# design.net
KiCad netlist of a schematic drawn in Altium Designer
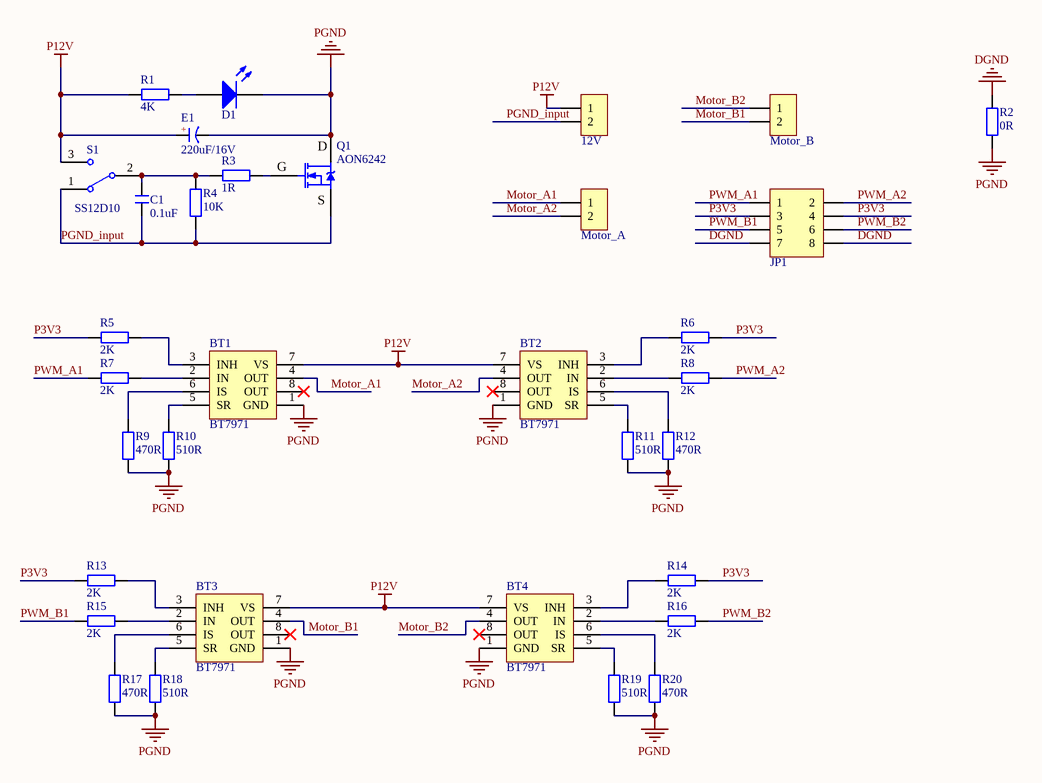
[diagram p0: 驱动开关.SchDoc]

(export (version "E")
  (design (tool "Eeschema 10.0.6"))
  (components
    (comp (ref "12V")
      (value "HDR-1X2")
      (footprint "KF301-5.0-2P")
      (description "2P接插件")
      (fields (field (name "版权归属") "封装库来自淘宝 ID：黄晶宝石"))
      (libsource (lib "6.0 - 接插件-脚距5.0") (part "Header 2"))
    )
    (comp (ref "BT1")
      (value "BT7971")
      (footprint "TO263-7A")
      (libsource (lib "altium-import") (part "root_0_BTN7971_"))
    )
    (comp (ref "BT2")
      (value "BT7971")
      (footprint "TO263-7A")
      (libsource (lib "altium-import") (part "root_0_mirrored_BTN7971_"))
    )
    (comp (ref "BT3")
      (value "BT7971")
      (footprint "TO263-7A")
      (libsource (lib "altium-import") (part "root_0_BTN7971_"))
    )
    (comp (ref "BT4")
      (value "BT7971")
      (footprint "TO263-7A")
      (libsource (lib "altium-import") (part "root_0_mirrored_BTN7971_"))
    )
    (comp (ref "C1")
      (value "0.1uF")
      (footprint "C 0603_L")
      (description "贴片电容")
      (libsource (lib "0.1 - 电阻-电容-电感") (part "C"))
    )
    (comp (ref "D1")
      (value "LED")
      (footprint "LED 0603B")
      (description "发光二极管")
      (libsource (lib "0.3 - LED发光二极管") (part "LED"))
    )
    (comp (ref "E1")
      (value "220uF/16V")
      (footprint "CM D(6.3*7.7)")
      (description "贴片电解电容")
      (libsource (lib "0.1 - 电阻-电容-电感") (part "CE_SMD"))
    )
    (comp (ref "JP1")
      (value "Header 4X2")
      (footprint "HDR2.54-LI-2x4P")
      (description "4*2P接插件")
      (libsource (lib "5.4 - 接插件-脚距2.54 (100mil) ") (part "Header 4X2"))
    )
    (comp (ref "Motor_A")
      (value "HDR-1X2")
      (footprint "KF301-5.0-2P")
      (description "2P接插件")
      (fields (field (name "版权归属") "封装库来自淘宝 ID：黄晶宝石"))
      (libsource (lib "6.0 - 接插件-脚距5.0") (part "Header 2"))
    )
    (comp (ref "Motor_B")
      (value "HDR-1X2")
      (footprint "KF301-5.0-2P")
      (description "2P接插件")
      (fields (field (name "版权归属") "封装库来自淘宝 ID：黄晶宝石"))
      (libsource (lib "6.0 - 接插件-脚距5.0") (part "Header 2"))
    )
    (comp (ref "Q1")
      (value "AON6242")
      (footprint "AON6242")
      (description "N沟场效应管")
      (libsource (lib "0.4 - 三极管-场效应管-可控硅") (part "IRF3710"))
    )
    (comp (ref "R1")
      (value "4K")
      (footprint "R 0603_L")
      (description "贴片电阻")
      (libsource (lib "0.1 - 电阻-电容-电感") (part "R"))
    )
    (comp (ref "R2")
      (value "0R")
      (footprint "R 0603_L")
      (description "贴片电阻")
      (libsource (lib "0.1 - 电阻-电容-电感") (part "R"))
    )
    (comp (ref "R3")
      (value "1R")
      (footprint "R 0603_L")
      (description "贴片电阻")
      (libsource (lib "0.1 - 电阻-电容-电感") (part "R"))
    )
    (comp (ref "R4")
      (value "10K")
      (footprint "R 0603_L")
      (description "贴片电阻")
      (libsource (lib "0.1 - 电阻-电容-电感") (part "R"))
    )
    (comp (ref "R5")
      (value "2K")
      (footprint "R 0603_L")
      (description "贴片电阻")
      (libsource (lib "0.1 - 电阻-电容-电感") (part "R"))
    )
    (comp (ref "R6")
      (value "2K")
      (footprint "R 0603_L")
      (description "贴片电阻")
      (libsource (lib "0.1 - 电阻-电容-电感") (part "R"))
    )
    (comp (ref "R7")
      (value "2K")
      (footprint "R 0603_L")
      (description "贴片电阻")
      (libsource (lib "0.1 - 电阻-电容-电感") (part "R"))
    )
    (comp (ref "R8")
      (value "2K")
      (footprint "R 0603_L")
      (description "贴片电阻")
      (libsource (lib "0.1 - 电阻-电容-电感") (part "R"))
    )
    (comp (ref "R9")
      (value "470R")
      (footprint "R 0603_L")
      (description "贴片电阻")
      (libsource (lib "0.1 - 电阻-电容-电感") (part "R"))
    )
    (comp (ref "R10")
      (value "510R")
      (footprint "R 0603_L")
      (description "贴片电阻")
      (libsource (lib "0.1 - 电阻-电容-电感") (part "R"))
    )
    (comp (ref "R11")
      (value "510R")
      (footprint "R 0603_L")
      (description "贴片电阻")
      (libsource (lib "0.1 - 电阻-电容-电感") (part "R"))
    )
    (comp (ref "R12")
      (value "470R")
      (footprint "R 0603_L")
      (description "贴片电阻")
      (libsource (lib "0.1 - 电阻-电容-电感") (part "R"))
    )
    (comp (ref "R13")
      (value "2K")
      (footprint "R 0603_L")
      (description "贴片电阻")
      (libsource (lib "0.1 - 电阻-电容-电感") (part "R"))
    )
    (comp (ref "R14")
      (value "2K")
      (footprint "R 0603_L")
      (description "贴片电阻")
      (libsource (lib "0.1 - 电阻-电容-电感") (part "R"))
    )
    (comp (ref "R15")
      (value "2K")
      (footprint "R 0603_L")
      (description "贴片电阻")
      (libsource (lib "0.1 - 电阻-电容-电感") (part "R"))
    )
    (comp (ref "R16")
      (value "2K")
      (footprint "R 0603_L")
      (description "贴片电阻")
      (libsource (lib "0.1 - 电阻-电容-电感") (part "R"))
    )
    (comp (ref "R17")
      (value "470R")
      (footprint "R 0603_L")
      (description "贴片电阻")
      (libsource (lib "0.1 - 电阻-电容-电感") (part "R"))
    )
    (comp (ref "R18")
      (value "510R")
      (footprint "R 0603_L")
      (description "贴片电阻")
      (libsource (lib "0.1 - 电阻-电容-电感") (part "R"))
    )
    (comp (ref "R19")
      (value "510R")
      (footprint "R 0603_L")
      (description "贴片电阻")
      (libsource (lib "0.1 - 电阻-电容-电感") (part "R"))
    )
    (comp (ref "R20")
      (value "470R")
      (footprint "R 0603_L")
      (description "贴片电阻")
      (libsource (lib "0.1 - 电阻-电容-电感") (part "R"))
    )
    (comp (ref "S1")
      (value "SS12D10")
      (footprint "SS-12D10")
      (description "MTS10x系列3脚扭子开关")
      (libsource (lib "0.7 - 常用按键-开关-蜂鸣器-电池") (part "MTS-10x"))
    )
  )
  (nets
    (net (code "1") (name "/Motor_A1") (class "Default")
      (node (ref "BT1") (pin "4") (pinfunction "OUT_4") (pintype "passive"))
      (node (ref "Motor_A") (pin "1") (pinfunction "1_1") (pintype "passive"))
    )
    (net (code "2") (name "/Motor_A2") (class "Default")
      (node (ref "BT2") (pin "4") (pinfunction "OUT_4") (pintype "passive"))
      (node (ref "Motor_A") (pin "2") (pinfunction "2_2") (pintype "passive"))
    )
    (net (code "3") (name "/Motor_B1") (class "Default")
      (node (ref "BT3") (pin "4") (pinfunction "OUT_4") (pintype "passive"))
      (node (ref "Motor_B") (pin "2") (pinfunction "2_2") (pintype "passive"))
    )
    (net (code "4") (name "/Motor_B2") (class "Default")
      (node (ref "BT4") (pin "4") (pinfunction "OUT_4") (pintype "passive"))
      (node (ref "Motor_B") (pin "1") (pinfunction "1_1") (pintype "passive"))
    )
    (net (code "5") (name "/P3V3") (class "Default")
      (node (ref "JP1") (pin "3") (pinfunction "3_3") (pintype "passive"))
      (node (ref "JP1") (pin "4") (pinfunction "4_4") (pintype "passive"))
      (node (ref "R13") (pin "1") (pinfunction "1_1") (pintype "passive"))
      (node (ref "R14") (pin "1") (pinfunction "1_1") (pintype "passive"))
      (node (ref "R5") (pin "1") (pinfunction "1_1") (pintype "passive"))
      (node (ref "R6") (pin "1") (pinfunction "1_1") (pintype "passive"))
    )
    (net (code "6") (name "/PGND_input") (class "Default")
      (node (ref "12V") (pin "2") (pinfunction "2_2") (pintype "passive"))
      (node (ref "C1") (pin "1") (pinfunction "1_1") (pintype "passive"))
      (node (ref "Q1") (pin "3") (pinfunction "S_3") (pintype "passive"))
      (node (ref "R4") (pin "1") (pinfunction "1_1") (pintype "passive"))
      (node (ref "S1") (pin "1") (pinfunction "1_1") (pintype "passive"))
    )
    (net (code "7") (name "/PWM_A1") (class "Default")
      (node (ref "JP1") (pin "1") (pinfunction "1_1") (pintype "passive"))
      (node (ref "R7") (pin "1") (pinfunction "1_1") (pintype "passive"))
    )
    (net (code "8") (name "/PWM_A2") (class "Default")
      (node (ref "JP1") (pin "2") (pinfunction "2_2") (pintype "passive"))
      (node (ref "R8") (pin "1") (pinfunction "1_1") (pintype "passive"))
    )
    (net (code "9") (name "/PWM_B1") (class "Default")
      (node (ref "JP1") (pin "5") (pinfunction "5_5") (pintype "passive"))
      (node (ref "R15") (pin "1") (pinfunction "1_1") (pintype "passive"))
    )
    (net (code "10") (name "/PWM_B2") (class "Default")
      (node (ref "JP1") (pin "6") (pinfunction "6_6") (pintype "passive"))
      (node (ref "R16") (pin "1") (pinfunction "1_1") (pintype "passive"))
    )
    (net (code "11") (name "DGND") (class "Default")
      (node (ref "JP1") (pin "7") (pinfunction "7_7") (pintype "passive"))
      (node (ref "JP1") (pin "8") (pinfunction "8_8") (pintype "passive"))
      (node (ref "R2") (pin "2") (pinfunction "2_2") (pintype "passive"))
    )
    (net (code "12") (name "Net-(BT1-IN)") (class "Default")
      (node (ref "BT1") (pin "2") (pinfunction "IN_2") (pintype "passive"))
      (node (ref "R7") (pin "2") (pinfunction "2_2") (pintype "passive"))
    )
    (net (code "13") (name "Net-(BT1-INH)") (class "Default")
      (node (ref "BT1") (pin "3") (pinfunction "INH_3") (pintype "passive"))
      (node (ref "R5") (pin "2") (pinfunction "2_2") (pintype "passive"))
    )
    (net (code "14") (name "Net-(BT1-IS)") (class "Default")
      (node (ref "BT1") (pin "6") (pinfunction "IS_6") (pintype "passive"))
      (node (ref "R9") (pin "2") (pinfunction "2_2") (pintype "passive"))
    )
    (net (code "15") (name "Net-(BT1-SR)") (class "Default")
      (node (ref "BT1") (pin "5") (pinfunction "SR_5") (pintype "passive"))
      (node (ref "R10") (pin "2") (pinfunction "2_2") (pintype "passive"))
    )
    (net (code "16") (name "Net-(BT2-IN)") (class "Default")
      (node (ref "BT2") (pin "2") (pinfunction "IN_2") (pintype "passive"))
      (node (ref "R8") (pin "2") (pinfunction "2_2") (pintype "passive"))
    )
    (net (code "17") (name "Net-(BT2-INH)") (class "Default")
      (node (ref "BT2") (pin "3") (pinfunction "INH_3") (pintype "passive"))
      (node (ref "R6") (pin "2") (pinfunction "2_2") (pintype "passive"))
    )
    (net (code "18") (name "Net-(BT2-IS)") (class "Default")
      (node (ref "BT2") (pin "6") (pinfunction "IS_6") (pintype "passive"))
      (node (ref "R12") (pin "1") (pinfunction "1_1") (pintype "passive"))
    )
    (net (code "19") (name "Net-(BT2-SR)") (class "Default")
      (node (ref "BT2") (pin "5") (pinfunction "SR_5") (pintype "passive"))
      (node (ref "R11") (pin "1") (pinfunction "1_1") (pintype "passive"))
    )
    (net (code "20") (name "Net-(BT3-IN)") (class "Default")
      (node (ref "BT3") (pin "2") (pinfunction "IN_2") (pintype "passive"))
      (node (ref "R15") (pin "2") (pinfunction "2_2") (pintype "passive"))
    )
    (net (code "21") (name "Net-(BT3-INH)") (class "Default")
      (node (ref "BT3") (pin "3") (pinfunction "INH_3") (pintype "passive"))
      (node (ref "R13") (pin "2") (pinfunction "2_2") (pintype "passive"))
    )
    (net (code "22") (name "Net-(BT3-IS)") (class "Default")
      (node (ref "BT3") (pin "6") (pinfunction "IS_6") (pintype "passive"))
      (node (ref "R17") (pin "2") (pinfunction "2_2") (pintype "passive"))
    )
    (net (code "23") (name "Net-(BT3-SR)") (class "Default")
      (node (ref "BT3") (pin "5") (pinfunction "SR_5") (pintype "passive"))
      (node (ref "R18") (pin "2") (pinfunction "2_2") (pintype "passive"))
    )
    (net (code "24") (name "Net-(BT4-IN)") (class "Default")
      (node (ref "BT4") (pin "2") (pinfunction "IN_2") (pintype "passive"))
      (node (ref "R16") (pin "2") (pinfunction "2_2") (pintype "passive"))
    )
    (net (code "25") (name "Net-(BT4-INH)") (class "Default")
      (node (ref "BT4") (pin "3") (pinfunction "INH_3") (pintype "passive"))
      (node (ref "R14") (pin "2") (pinfunction "2_2") (pintype "passive"))
    )
    (net (code "26") (name "Net-(BT4-IS)") (class "Default")
      (node (ref "BT4") (pin "6") (pinfunction "IS_6") (pintype "passive"))
      (node (ref "R20") (pin "1") (pinfunction "1_1") (pintype "passive"))
    )
    (net (code "27") (name "Net-(BT4-SR)") (class "Default")
      (node (ref "BT4") (pin "5") (pinfunction "SR_5") (pintype "passive"))
      (node (ref "R19") (pin "1") (pinfunction "1_1") (pintype "passive"))
    )
    (net (code "28") (name "Net-(C1-Pad2)") (class "Default")
      (node (ref "C1") (pin "2") (pinfunction "2_2") (pintype "passive"))
      (node (ref "R3") (pin "1") (pinfunction "1_1") (pintype "passive"))
      (node (ref "R4") (pin "2") (pinfunction "2_2") (pintype "passive"))
      (node (ref "S1") (pin "2") (pinfunction "2_2") (pintype "passive"))
    )
    (net (code "29") (name "Net-(D1-A)") (class "Default")
      (node (ref "D1") (pin "1") (pinfunction "A_1") (pintype "passive"))
      (node (ref "R1") (pin "1") (pinfunction "1_1") (pintype "passive"))
    )
    (net (code "30") (name "Net-(Q1-G)") (class "Default")
      (node (ref "Q1") (pin "1") (pinfunction "G_1") (pintype "passive"))
      (node (ref "R3") (pin "2") (pinfunction "2_2") (pintype "passive"))
    )
    (net (code "31") (name "P12V") (class "Default")
      (node (ref "12V") (pin "1") (pinfunction "1_1") (pintype "passive"))
      (node (ref "BT1") (pin "7") (pinfunction "VS_7") (pintype "passive"))
      (node (ref "BT2") (pin "7") (pinfunction "VS_7") (pintype "passive"))
      (node (ref "BT3") (pin "7") (pinfunction "VS_7") (pintype "passive"))
      (node (ref "BT4") (pin "7") (pinfunction "VS_7") (pintype "passive"))
      (node (ref "E1") (pin "1") (pinfunction "A_1") (pintype "passive"))
      (node (ref "R1") (pin "2") (pinfunction "2_2") (pintype "passive"))
      (node (ref "S1") (pin "3") (pinfunction "3_3") (pintype "passive"))
    )
    (net (code "32") (name "PGND") (class "Default")
      (node (ref "BT1") (pin "1") (pinfunction "GND_1") (pintype "passive"))
      (node (ref "BT2") (pin "1") (pinfunction "GND_1") (pintype "passive"))
      (node (ref "BT3") (pin "1") (pinfunction "GND_1") (pintype "passive"))
      (node (ref "BT4") (pin "1") (pinfunction "GND_1") (pintype "passive"))
      (node (ref "D1") (pin "2") (pinfunction "K_2") (pintype "passive"))
      (node (ref "E1") (pin "2") (pinfunction "K_2") (pintype "passive"))
      (node (ref "Q1") (pin "2") (pinfunction "D_2") (pintype "passive"))
      (node (ref "R10") (pin "1") (pinfunction "1_1") (pintype "passive"))
      (node (ref "R11") (pin "2") (pinfunction "2_2") (pintype "passive"))
      (node (ref "R12") (pin "2") (pinfunction "2_2") (pintype "passive"))
      (node (ref "R17") (pin "1") (pinfunction "1_1") (pintype "passive"))
      (node (ref "R18") (pin "1") (pinfunction "1_1") (pintype "passive"))
      (node (ref "R19") (pin "2") (pinfunction "2_2") (pintype "passive"))
      (node (ref "R2") (pin "1") (pinfunction "1_1") (pintype "passive"))
      (node (ref "R20") (pin "2") (pinfunction "2_2") (pintype "passive"))
      (node (ref "R9") (pin "1") (pinfunction "1_1") (pintype "passive"))
    )
    (net (code "33") (name "unconnected-(BT1-OUT-Pad8)") (class "Default")
      (node (ref "BT1") (pin "8") (pinfunction "OUT_8") (pintype "passive+no_connect"))
    )
    (net (code "34") (name "unconnected-(BT2-OUT-Pad8)") (class "Default")
      (node (ref "BT2") (pin "8") (pinfunction "OUT_8") (pintype "passive+no_connect"))
    )
    (net (code "35") (name "unconnected-(BT3-OUT-Pad8)") (class "Default")
      (node (ref "BT3") (pin "8") (pinfunction "OUT_8") (pintype "passive+no_connect"))
    )
    (net (code "36") (name "unconnected-(BT4-OUT-Pad8)") (class "Default")
      (node (ref "BT4") (pin "8") (pinfunction "OUT_8") (pintype "passive+no_connect"))
    )
  )
)
